# 03_GSM_GPRS_GPS.net
KiCad netlist of a schematic drawn in Altium Designer
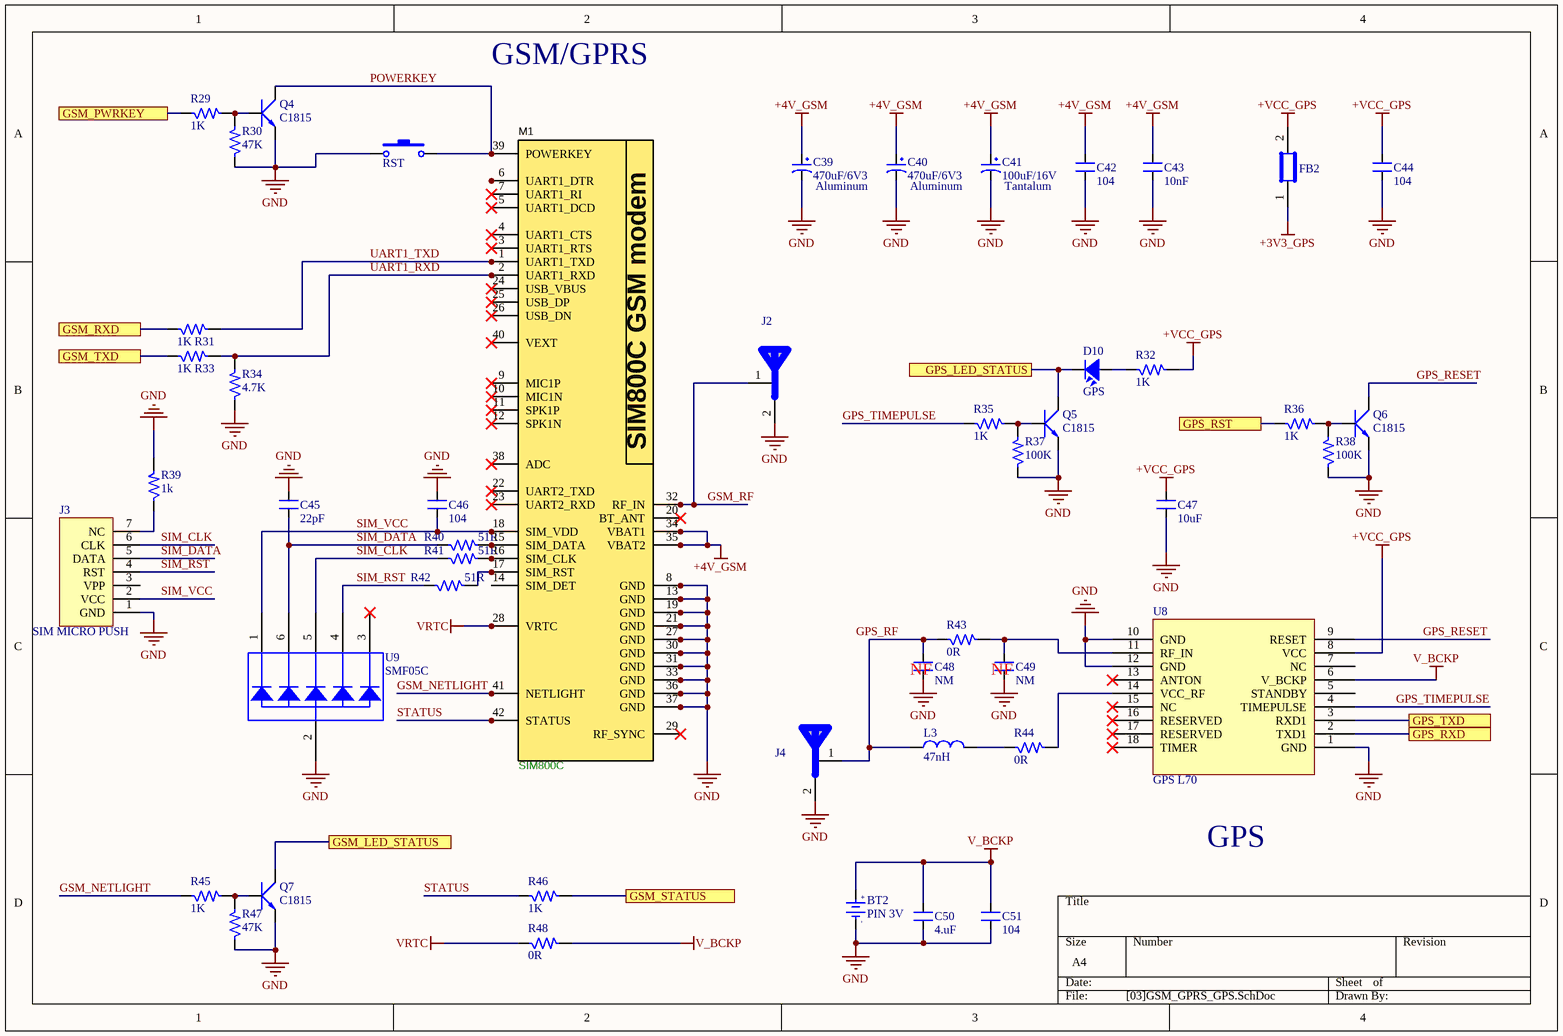
[diagram p0: [03]GSM_GPRS_GPS.SchDoc]

(export (version "E")
  (design (tool "Eeschema 10.0.6"))
  (components
    (comp (ref "BT2")
      (value "PIN 3V")
      (footprint "My Library:CR1220 SMD")
      (description "Battery 3VDC")
      (libsource (lib "GPS_Traking_V1_1") (part "PIN 3V"))
    )
    (comp (ref "C39")
      (value "470uF/6V3")
      (footprint "C_Alu_6.3x7.7")
      (description "Cap Aluminum")
      (libsource (lib "GPS_Traking_V1_1") (part "C-Alu-Tantalum"))
    )
    (comp (ref "C40")
      (value "470uF/6V3")
      (footprint "C_Alu_6.3x7.7")
      (description "Cap Aluminum")
      (libsource (lib "GPS_Traking_V1_1") (part "C-Alu-Tantalum"))
    )
    (comp (ref "C41")
      (value "100uF/16V")
      (footprint "C_7343_40")
      (description "Cap Tantalum 7343")
      (libsource (lib "GPS_Traking_V1_1") (part "C-Alu-Tantalum"))
    )
    (comp (ref "C42")
      (value "104")
      (footprint "CAP_0805")
      (description "Cap SMD")
      (libsource (lib "GPS_Traking_V1_1") (part "CM"))
    )
    (comp (ref "C43")
      (value "10nF")
      (footprint "CAP_0805")
      (description "Cap SMD")
      (libsource (lib "GPS_Traking_V1_1") (part "CM"))
    )
    (comp (ref "C44")
      (value "104")
      (footprint "CAP_0805")
      (description "Cap SMD")
      (libsource (lib "GPS_Traking_V1_1") (part "CM"))
    )
    (comp (ref "C45")
      (value "22pF")
      (footprint "C0603 SMT")
      (description "Cap SMD")
      (libsource (lib "GPS_Traking_V1_1") (part "CM"))
    )
    (comp (ref "C46")
      (value "104")
      (footprint "C0603 SMT")
      (description "Cap SMD")
      (libsource (lib "GPS_Traking_V1_1") (part "CM"))
    )
    (comp (ref "C47")
      (value "10uF")
      (footprint "CAP_0805")
      (description "Cap SMD")
      (libsource (lib "GPS_Traking_V1_1") (part "CM"))
    )
    (comp (ref "C48")
      (value "NM")
      (footprint "C0603 SMT")
      (description "Cap SMD")
      (libsource (lib "GPS_Traking_V1_1") (part "CM"))
    )
    (comp (ref "C49")
      (value "NM")
      (footprint "C0603 SMT")
      (description "Cap SMD")
      (libsource (lib "GPS_Traking_V1_1") (part "CM"))
    )
    (comp (ref "C50")
      (value "4.uF")
      (footprint "SM-1210")
      (description "Cap SMD")
      (libsource (lib "GPS_Traking_V1_1") (part "CM"))
    )
    (comp (ref "C51")
      (value "104")
      (footprint "CAP_0805")
      (description "Cap SMD")
      (libsource (lib "GPS_Traking_V1_1") (part "CM"))
    )
    (comp (ref "D10")
      (value "GPS")
      (footprint "LED-0805-Red")
      (description "LED Single colour Green and Red")
      (libsource (lib "GPS_Traking_V1_1") (part "LED"))
    )
    (comp (ref "FB2")
      (value "BLM21PG600SN1D")
      (footprint "R0805")
      (description "Ferrite Bead")
      (libsource (lib "GPS_Traking_V1_1") (part "Ferrite Bead"))
    )
    (comp (ref "J2")
      (value "GPS_ANTENNA")
      (footprint "Antenna-MCX5.08-H5")
      (libsource (lib "GPS_Traking_V1_1") (part "ANTEN"))
    )
    (comp (ref "J3")
      (value "SIM MICRO PUSH")
      (footprint "My Library:MICROSIM_PUSH")
      (libsource (lib "My Library") (part "SIM MICRO PUSH"))
    )
    (comp (ref "J4")
      (value "GPS_ANTENNA")
      (footprint "Antenna-MCX5.08-H5")
      (libsource (lib "GPS_Traking_V1_1") (part "ANTEN"))
    )
    (comp (ref "L3")
      (value "47nH")
      (footprint "RES-SMD-0805")
      (description "Inductor")
      (libsource (lib "GPS_Traking_V1_1") (part "L1"))
    )
    (comp (ref "M1")
      (value "SIM800C")
      (footprint "SIM800C")
      (libsource (lib "GPS_Traking_V1_1") (part "SIM800C"))
    )
    (comp (ref "Q4")
      (value "C1815")
      (footprint "SOT23B")
      (description "NPN 600mW, ECB")
      (libsource (lib "GPS_Traking_V1_1") (part "C1815"))
    )
    (comp (ref "Q5")
      (value "C1815")
      (footprint "SOT23B")
      (description "NPN 600mW, ECB")
      (libsource (lib "GPS_Traking_V1_1") (part "C1815"))
    )
    (comp (ref "Q6")
      (value "C1815")
      (footprint "SOT23B")
      (description "NPN 600mW, ECB")
      (libsource (lib "GPS_Traking_V1_1") (part "C1815"))
    )
    (comp (ref "Q7")
      (value "C1815")
      (footprint "SOT23B")
      (description "NPN 600mW, ECB")
      (libsource (lib "GPS_Traking_V1_1") (part "C1815"))
    )
    (comp (ref "R29")
      (value "1K")
      (footprint "R0603 -SMT")
      (description "Resistor SMD")
      (libsource (lib "GPS_Traking_V1_1") (part "RM"))
    )
    (comp (ref "R30")
      (value "47K")
      (footprint "R0603 -SMT")
      (description "Resistor SMD")
      (libsource (lib "GPS_Traking_V1_1") (part "RM"))
    )
    (comp (ref "R31")
      (value "1K")
      (footprint "R0603 -SMT")
      (description "Resistor SMD")
      (libsource (lib "GPS_Traking_V1_1") (part "RM"))
    )
    (comp (ref "R32")
      (value "1K")
      (footprint "RES-SMD-0805")
      (description "Resistor SMD")
      (libsource (lib "GPS_Traking_V1_1") (part "RM"))
    )
    (comp (ref "R33")
      (value "1K")
      (footprint "R0603 -SMT")
      (description "Resistor SMD")
      (libsource (lib "GPS_Traking_V1_1") (part "RM"))
    )
    (comp (ref "R34")
      (value "4.7K")
      (footprint "R0603 -SMT")
      (description "Resistor SMD")
      (libsource (lib "GPS_Traking_V1_1") (part "RM"))
    )
    (comp (ref "R35")
      (value "1K")
      (footprint "RES-SMD-0805")
      (description "Resistor SMD")
      (libsource (lib "GPS_Traking_V1_1") (part "RM"))
    )
    (comp (ref "R36")
      (value "1K")
      (footprint "RES-SMD-0805")
      (description "Resistor SMD")
      (libsource (lib "GPS_Traking_V1_1") (part "RM"))
    )
    (comp (ref "R37")
      (value "100K")
      (footprint "RES-SMD-0805")
      (description "Resistor SMD")
      (libsource (lib "GPS_Traking_V1_1") (part "RM"))
    )
    (comp (ref "R38")
      (value "100K")
      (footprint "RES-SMD-0805")
      (description "Resistor SMD")
      (libsource (lib "GPS_Traking_V1_1") (part "RM"))
    )
    (comp (ref "R39")
      (value "1k")
      (footprint "RES-SMD-0805")
      (description "Resistor SMD")
      (libsource (lib "GPS_Traking_V1_1") (part "RM"))
    )
    (comp (ref "R40")
      (value "51R")
      (footprint "R0603 -SMT")
      (description "Resistor SMD")
      (libsource (lib "GPS_Traking_V1_1") (part "RM"))
    )
    (comp (ref "R41")
      (value "51R")
      (footprint "R0603 -SMT")
      (description "Resistor SMD")
      (libsource (lib "GPS_Traking_V1_1") (part "RM"))
    )
    (comp (ref "R42")
      (value "51R")
      (footprint "R0603 -SMT")
      (description "Resistor SMD")
      (libsource (lib "GPS_Traking_V1_1") (part "RM"))
    )
    (comp (ref "R43")
      (value "0R")
      (footprint "R0603 -SMT")
      (description "Resistor SMD")
      (libsource (lib "GPS_Traking_V1_1") (part "RM"))
    )
    (comp (ref "R44")
      (value "0R")
      (footprint "R0603 -SMT")
      (description "Resistor SMD")
      (libsource (lib "GPS_Traking_V1_1") (part "RM"))
    )
    (comp (ref "R45")
      (value "1K")
      (footprint "R0603 -SMT")
      (description "Resistor SMD")
      (libsource (lib "GPS_Traking_V1_1") (part "RM"))
    )
    (comp (ref "R46")
      (value "1K")
      (footprint "R0603 -SMT")
      (description "Resistor SMD")
      (libsource (lib "GPS_Traking_V1_1") (part "RM"))
    )
    (comp (ref "R47")
      (value "47K")
      (footprint "R0603 -SMT")
      (description "Resistor SMD")
      (libsource (lib "GPS_Traking_V1_1") (part "RM"))
    )
    (comp (ref "R48")
      (value "0R")
      (footprint "RES-SMD-0805")
      (description "Resistor SMD")
      (libsource (lib "GPS_Traking_V1_1") (part "RM"))
    )
    (comp (ref "RST")
      (value "SW-SMD")
      (footprint "SW-SMD")
      (description "Switch")
      (fields (field (name "PUBLISHER") "Altium Limited"))
      (libsource (lib "My Library") (part "SW-SMD"))
    )
    (comp (ref "U8")
      (value "GPS L70")
      (footprint "GPS L70")
      (libsource (lib "GPS_Traking_V1_1") (part "GPS L70"))
    )
    (comp (ref "U9")
      (value "SMF05C")
      (footprint "SOT_363_6")
      (description "ESD Protection")
      (libsource (lib "GPS_Traking_V1_1") (part "SMF05C"))
    )
  )
  (nets
    (net (code "1") (name "+3V3_GPS") (class "Default")
      (node (ref "FB2") (pin "1") (pinfunction "1_1") (pintype "passive"))
    )
    (net (code "2") (name "+4V_GSM") (class "Default")
      (node (ref "C39") (pin "1") (pinfunction "1_1") (pintype "passive"))
      (node (ref "C40") (pin "1") (pinfunction "1_1") (pintype "passive"))
      (node (ref "C41") (pin "1") (pinfunction "1_1") (pintype "passive"))
      (node (ref "C42") (pin "1") (pinfunction "1_1") (pintype "passive"))
      (node (ref "C43") (pin "1") (pinfunction "1_1") (pintype "passive"))
      (node (ref "M1") (pin "34") (pinfunction "VBAT1_34") (pintype "passive"))
      (node (ref "M1") (pin "35") (pinfunction "VBAT2_35") (pintype "passive"))
    )
    (net (code "3") (name "+VCC_GPS") (class "Default")
      (node (ref "C44") (pin "2") (pinfunction "2_2") (pintype "passive"))
      (node (ref "C47") (pin "2") (pinfunction "2_2") (pintype "passive"))
      (node (ref "FB2") (pin "2") (pinfunction "2_2") (pintype "passive"))
      (node (ref "R32") (pin "2") (pinfunction "2_2") (pintype "passive"))
      (node (ref "U8") (pin "8") (pinfunction "VCC_8") (pintype "passive"))
    )
    (net (code "4") (name "/GPS_LED_STATUS") (class "Default")
      (node (ref "D10") (pin "2") (pinfunction "2_2") (pintype "passive"))
      (node (ref "Q5") (pin "2") (pinfunction "C_2") (pintype "passive"))
    )
    (net (code "5") (name "/GPS_RESET") (class "Default")
      (node (ref "Q6") (pin "2") (pinfunction "C_2") (pintype "passive"))
      (node (ref "U8") (pin "9") (pinfunction "RESET_9") (pintype "passive"))
    )
    (net (code "7") (name "/GPS_RST") (class "Default")
      (node (ref "R36") (pin "1") (pinfunction "1_1") (pintype "passive"))
    )
    (net (code "8") (name "/GPS_RXD") (class "Default")
      (node (ref "U8") (pin "2") (pinfunction "TXD1_2") (pintype "passive"))
    )
    (net (code "9") (name "/GPS_TIMEPULSE") (class "Default")
      (node (ref "R35") (pin "1") (pinfunction "1_1") (pintype "passive"))
      (node (ref "U8") (pin "4") (pinfunction "TIMEPULSE_4") (pintype "passive"))
    )
    (net (code "10") (name "/GPS_TXD") (class "Default")
      (node (ref "U8") (pin "3") (pinfunction "RXD1_3") (pintype "passive"))
    )
    (net (code "11") (name "/GSM_LED_STATUS") (class "Default")
      (node (ref "Q7") (pin "2") (pinfunction "C_2") (pintype "passive"))
    )
    (net (code "12") (name "/GSM_NETLIGHT") (class "Default")
      (node (ref "M1") (pin "41") (pinfunction "NETLIGHT_41") (pintype "passive"))
      (node (ref "R45") (pin "1") (pinfunction "1_1") (pintype "passive"))
    )
    (net (code "13") (name "/GSM_PWRKEY") (class "Default")
      (node (ref "R29") (pin "1") (pinfunction "1_1") (pintype "passive"))
    )
    (net (code "14") (name "/GSM_RF") (class "Default")
      (node (ref "J2") (pin "1") (pinfunction "GND_1") (pintype "passive"))
      (node (ref "M1") (pin "32") (pinfunction "RF_IN_32") (pintype "passive"))
    )
    (net (code "15") (name "/GSM_RXD") (class "Default")
      (node (ref "R31") (pin "1") (pinfunction "1_1") (pintype "passive"))
    )
    (net (code "16") (name "/GSM_STATUS") (class "Default")
      (node (ref "R46") (pin "2") (pinfunction "2_2") (pintype "passive"))
    )
    (net (code "17") (name "/GSM_TXD") (class "Default")
      (node (ref "R33") (pin "1") (pinfunction "1_1") (pintype "passive"))
    )
    (net (code "18") (name "/POWERKEY") (class "Default")
      (node (ref "M1") (pin "39") (pinfunction "POWERKEY_39") (pintype "passive"))
      (node (ref "Q4") (pin "2") (pinfunction "C_2") (pintype "passive"))
      (node (ref "RST") (pin "2") (pinfunction "2_2") (pintype "passive"))
    )
    (net (code "19") (name "/SIM_CLK") (class "Default")
      (node (ref "J3") (pin "6") (pinfunction "CLK_6") (pintype "passive"))
      (node (ref "R41") (pin "1") (pinfunction "1_1") (pintype "passive"))
      (node (ref "U9") (pin "5") (pinfunction "K4_5") (pintype "power_in"))
    )
    (net (code "20") (name "/SIM_DATA") (class "Default")
      (node (ref "C45") (pin "1") (pinfunction "1_1") (pintype "passive"))
      (node (ref "J3") (pin "5") (pinfunction "DATA_5") (pintype "passive"))
      (node (ref "R40") (pin "1") (pinfunction "1_1") (pintype "passive"))
      (node (ref "U9") (pin "6") (pinfunction "K5_6") (pintype "passive"))
    )
    (net (code "21") (name "/SIM_RST") (class "Default")
      (node (ref "J3") (pin "4") (pinfunction "RST_4") (pintype "passive"))
      (node (ref "R42") (pin "1") (pinfunction "1_1") (pintype "passive"))
      (node (ref "U9") (pin "4") (pinfunction "K3_4") (pintype "passive"))
    )
    (net (code "22") (name "/SIM_VCC") (class "Default")
      (node (ref "C46") (pin "1") (pinfunction "1_1") (pintype "passive"))
      (node (ref "J3") (pin "2") (pinfunction "VCC_2") (pintype "passive"))
      (node (ref "M1") (pin "18") (pinfunction "SIM_VDD_18") (pintype "passive"))
      (node (ref "U9") (pin "1") (pinfunction "K1_1") (pintype "passive"))
    )
    (net (code "23") (name "/STATUS") (class "Default")
      (node (ref "M1") (pin "42") (pinfunction "STATUS_42") (pintype "passive"))
      (node (ref "R46") (pin "1") (pinfunction "1_1") (pintype "passive"))
    )
    (net (code "24") (name "/UART1_RXD") (class "Default")
      (node (ref "M1") (pin "2") (pinfunction "UART1_RXD_2") (pintype "passive"))
      (node (ref "R33") (pin "2") (pinfunction "2_2") (pintype "passive"))
      (node (ref "R34") (pin "2") (pinfunction "2_2") (pintype "passive"))
    )
    (net (code "25") (name "/UART1_TXD") (class "Default")
      (node (ref "M1") (pin "1") (pinfunction "UART1_TXD_1") (pintype "passive"))
      (node (ref "R31") (pin "2") (pinfunction "2_2") (pintype "passive"))
    )
    (net (code "26") (name "GND") (class "Default")
      (node (ref "BT2") (pin "2") (pinfunction "GND_2") (pintype "passive"))
      (node (ref "C39") (pin "2") (pinfunction "2_2") (pintype "passive"))
      (node (ref "C40") (pin "2") (pinfunction "2_2") (pintype "passive"))
      (node (ref "C41") (pin "2") (pinfunction "2_2") (pintype "passive"))
      (node (ref "C42") (pin "2") (pinfunction "2_2") (pintype "passive"))
      (node (ref "C43") (pin "2") (pinfunction "2_2") (pintype "passive"))
      (node (ref "C44") (pin "1") (pinfunction "1_1") (pintype "passive"))
      (node (ref "C45") (pin "2") (pinfunction "2_2") (pintype "passive"))
      (node (ref "C46") (pin "2") (pinfunction "2_2") (pintype "passive"))
      (node (ref "C47") (pin "1") (pinfunction "1_1") (pintype "passive"))
      (node (ref "C48") (pin "1") (pinfunction "1_1") (pintype "passive"))
      (node (ref "C49") (pin "1") (pinfunction "1_1") (pintype "passive"))
      (node (ref "C50") (pin "1") (pinfunction "1_1") (pintype "passive"))
      (node (ref "C51") (pin "1") (pinfunction "1_1") (pintype "passive"))
      (node (ref "J2") (pin "2") (pinfunction "GND_2") (pintype "passive"))
      (node (ref "J3") (pin "1") (pinfunction "GND_1") (pintype "passive"))
      (node (ref "J4") (pin "2") (pinfunction "GND_2") (pintype "passive"))
      (node (ref "M1") (pin "13") (pinfunction "GND_13") (pintype "passive"))
      (node (ref "M1") (pin "19") (pinfunction "GND_19") (pintype "passive"))
      (node (ref "M1") (pin "21") (pinfunction "GND_21") (pintype "passive"))
      (node (ref "M1") (pin "27") (pinfunction "GND_27") (pintype "passive"))
      (node (ref "M1") (pin "30") (pinfunction "GND_30") (pintype "passive"))
      (node (ref "M1") (pin "31") (pinfunction "GND_31") (pintype "passive"))
      (node (ref "M1") (pin "33") (pinfunction "GND_33") (pintype "passive"))
      (node (ref "M1") (pin "36") (pinfunction "GND_36") (pintype "passive"))
      (node (ref "M1") (pin "37") (pinfunction "GND_37") (pintype "passive"))
      (node (ref "M1") (pin "8") (pinfunction "GND_8") (pintype "passive"))
      (node (ref "Q4") (pin "1") (pinfunction "E_1") (pintype "passive"))
      (node (ref "Q5") (pin "1") (pinfunction "E_1") (pintype "passive"))
      (node (ref "Q6") (pin "1") (pinfunction "E_1") (pintype "passive"))
      (node (ref "Q7") (pin "1") (pinfunction "E_1") (pintype "passive"))
      (node (ref "R30") (pin "1") (pinfunction "1_1") (pintype "passive"))
      (node (ref "R34") (pin "1") (pinfunction "1_1") (pintype "passive"))
      (node (ref "R37") (pin "1") (pinfunction "1_1") (pintype "passive"))
      (node (ref "R38") (pin "1") (pinfunction "1_1") (pintype "passive"))
      (node (ref "R39") (pin "2") (pinfunction "2_2") (pintype "passive"))
      (node (ref "R47") (pin "1") (pinfunction "1_1") (pintype "passive"))
      (node (ref "RST") (pin "1") (pinfunction "1_1") (pintype "passive"))
      (node (ref "U8") (pin "1") (pinfunction "GND_1") (pintype "passive"))
      (node (ref "U8") (pin "10") (pinfunction "GND_10") (pintype "passive"))
      (node (ref "U8") (pin "12") (pinfunction "GND_12") (pintype "passive"))
      (node (ref "U9") (pin "2") (pinfunction "A_2") (pintype "power_in"))
    )
    (net (code "27") (name "Net-(C48-Pad2)") (class "Default")
      (node (ref "C48") (pin "2") (pinfunction "2_2") (pintype "passive"))
      (node (ref "J4") (pin "1") (pinfunction "GND_1") (pintype "passive"))
      (node (ref "L3") (pin "1") (pinfunction "1_1") (pintype "passive"))
      (node (ref "R43") (pin "1") (pinfunction "1_1") (pintype "passive"))
    )
    (net (code "28") (name "Net-(D10-Pad1)") (class "Default")
      (node (ref "D10") (pin "1") (pinfunction "1_1") (pintype "passive"))
      (node (ref "R32") (pin "1") (pinfunction "1_1") (pintype "passive"))
    )
    (net (code "29") (name "Net-(J3-NC)") (class "Default")
      (node (ref "J3") (pin "7") (pinfunction "NC_7") (pintype "passive"))
      (node (ref "R39") (pin "1") (pinfunction "1_1") (pintype "passive"))
    )
    (net (code "30") (name "Net-(L3-Pad2)") (class "Default")
      (node (ref "L3") (pin "2") (pinfunction "2_2") (pintype "passive"))
      (node (ref "R44") (pin "1") (pinfunction "1_1") (pintype "passive"))
    )
    (net (code "31") (name "Net-(M1-SIM_CLK)") (class "Default")
      (node (ref "M1") (pin "16") (pinfunction "SIM_CLK_16") (pintype "passive"))
      (node (ref "R41") (pin "2") (pinfunction "2_2") (pintype "passive"))
    )
    (net (code "32") (name "Net-(M1-SIM_DATA)") (class "Default")
      (node (ref "M1") (pin "15") (pinfunction "SIM_DATA_15") (pintype "passive"))
      (node (ref "R40") (pin "2") (pinfunction "2_2") (pintype "passive"))
    )
    (net (code "33") (name "Net-(M1-SIM_RST)") (class "Default")
      (node (ref "M1") (pin "17") (pinfunction "SIM_RST_17") (pintype "passive"))
      (node (ref "R42") (pin "2") (pinfunction "2_2") (pintype "passive"))
    )
    (net (code "34") (name "Net-(Q4-B)") (class "Default")
      (node (ref "Q4") (pin "3") (pinfunction "B_3") (pintype "passive"))
      (node (ref "R29") (pin "2") (pinfunction "2_2") (pintype "passive"))
      (node (ref "R30") (pin "2") (pinfunction "2_2") (pintype "passive"))
    )
    (net (code "35") (name "Net-(Q5-B)") (class "Default")
      (node (ref "Q5") (pin "3") (pinfunction "B_3") (pintype "passive"))
      (node (ref "R35") (pin "2") (pinfunction "2_2") (pintype "passive"))
      (node (ref "R37") (pin "2") (pinfunction "2_2") (pintype "passive"))
    )
    (net (code "36") (name "Net-(Q6-B)") (class "Default")
      (node (ref "Q6") (pin "3") (pinfunction "B_3") (pintype "passive"))
      (node (ref "R36") (pin "2") (pinfunction "2_2") (pintype "passive"))
      (node (ref "R38") (pin "2") (pinfunction "2_2") (pintype "passive"))
    )
    (net (code "37") (name "Net-(Q7-B)") (class "Default")
      (node (ref "Q7") (pin "3") (pinfunction "B_3") (pintype "passive"))
      (node (ref "R45") (pin "2") (pinfunction "2_2") (pintype "passive"))
      (node (ref "R47") (pin "2") (pinfunction "2_2") (pintype "passive"))
    )
    (net (code "38") (name "Net-(U8-RF_IN)") (class "Default")
      (node (ref "C49") (pin "2") (pinfunction "2_2") (pintype "passive"))
      (node (ref "R43") (pin "2") (pinfunction "2_2") (pintype "passive"))
      (node (ref "U8") (pin "11") (pinfunction "RF_IN_11") (pintype "passive"))
    )
    (net (code "39") (name "Net-(U8-VCC_RF)") (class "Default")
      (node (ref "R44") (pin "2") (pinfunction "2_2") (pintype "passive"))
      (node (ref "U8") (pin "14") (pinfunction "VCC_RF_14") (pintype "passive"))
    )
    (net (code "40") (name "VRTC") (class "Default")
      (node (ref "M1") (pin "28") (pinfunction "VRTC_28") (pintype "passive"))
      (node (ref "R48") (pin "1") (pinfunction "1_1") (pintype "passive"))
    )
    (net (code "41") (name "V_BCKP") (class "Default")
      (node (ref "BT2") (pin "1") (pinfunction "+3V_1") (pintype "passive"))
      (node (ref "C50") (pin "2") (pinfunction "2_2") (pintype "passive"))
      (node (ref "C51") (pin "2") (pinfunction "2_2") (pintype "passive"))
      (node (ref "R48") (pin "2") (pinfunction "2_2") (pintype "passive"))
      (node (ref "U8") (pin "6") (pinfunction "V_BCKP_6") (pintype "passive"))
    )
    (net (code "42") (name "unconnected-(J3-VPP-Pad3)") (class "Default")
      (node (ref "J3") (pin "3") (pinfunction "VPP_3") (pintype "passive"))
    )
    (net (code "43") (name "unconnected-(M1-ADC-Pad38)") (class "Default")
      (node (ref "M1") (pin "38") (pinfunction "ADC_38") (pintype "passive+no_connect"))
    )
    (net (code "44") (name "unconnected-(M1-BT_ANT-Pad20)") (class "Default")
      (node (ref "M1") (pin "20") (pinfunction "BT_ANT_20") (pintype "passive+no_connect"))
    )
    (net (code "45") (name "unconnected-(M1-MIC1N-Pad10)") (class "Default")
      (node (ref "M1") (pin "10") (pinfunction "MIC1N_10") (pintype "passive+no_connect"))
    )
    (net (code "46") (name "unconnected-(M1-MIC1P-Pad9)") (class "Default")
      (node (ref "M1") (pin "9") (pinfunction "MIC1P_9") (pintype "passive+no_connect"))
    )
    (net (code "47") (name "unconnected-(M1-RF_SYNC-Pad29)") (class "Default")
      (node (ref "M1") (pin "29") (pinfunction "RF_SYNC_29") (pintype "passive+no_connect"))
    )
    (net (code "48") (name "unconnected-(M1-SIM_DET-Pad14)") (class "Default")
      (node (ref "M1") (pin "14") (pinfunction "SIM_DET_14") (pintype "passive"))
    )
    (net (code "49") (name "unconnected-(M1-SPK1N-Pad12)") (class "Default")
      (node (ref "M1") (pin "12") (pinfunction "SPK1N_12") (pintype "passive+no_connect"))
    )
    (net (code "50") (name "unconnected-(M1-SPK1P-Pad11)") (class "Default")
      (node (ref "M1") (pin "11") (pinfunction "SPK1P_11") (pintype "passive+no_connect"))
    )
    (net (code "51") (name "unconnected-(M1-UART1_CTS-Pad4)") (class "Default")
      (node (ref "M1") (pin "4") (pinfunction "UART1_CTS_4") (pintype "passive+no_connect"))
    )
    (net (code "52") (name "unconnected-(M1-UART1_DCD-Pad5)") (class "Default")
      (node (ref "M1") (pin "5") (pinfunction "UART1_DCD_5") (pintype "passive+no_connect"))
    )
    (net (code "53") (name "unconnected-(M1-UART1_DTR-Pad6)") (class "Default")
      (node (ref "M1") (pin "6") (pinfunction "UART1_DTR_6") (pintype "passive"))
    )
    (net (code "54") (name "unconnected-(M1-UART1_RI-Pad7)") (class "Default")
      (node (ref "M1") (pin "7") (pinfunction "UART1_RI_7") (pintype "passive+no_connect"))
    )
    (net (code "55") (name "unconnected-(M1-UART1_RTS-Pad3)") (class "Default")
      (node (ref "M1") (pin "3") (pinfunction "UART1_RTS_3") (pintype "passive+no_connect"))
    )
    (net (code "56") (name "unconnected-(M1-UART2_RXD-Pad23)") (class "Default")
      (node (ref "M1") (pin "23") (pinfunction "UART2_RXD_23") (pintype "passive+no_connect"))
    )
    (net (code "57") (name "unconnected-(M1-UART2_TXD-Pad22)") (class "Default")
      (node (ref "M1") (pin "22") (pinfunction "UART2_TXD_22") (pintype "passive+no_connect"))
    )
    (net (code "58") (name "unconnected-(M1-USB_DN-Pad26)") (class "Default")
      (node (ref "M1") (pin "26") (pinfunction "USB_DN_26") (pintype "passive+no_connect"))
    )
    (net (code "59") (name "unconnected-(M1-USB_DP-Pad25)") (class "Default")
      (node (ref "M1") (pin "25") (pinfunction "USB_DP_25") (pintype "passive+no_connect"))
    )
    (net (code "60") (name "unconnected-(M1-USB_VBUS-Pad24)") (class "Default")
      (node (ref "M1") (pin "24") (pinfunction "USB_VBUS_24") (pintype "passive+no_connect"))
    )
    (net (code "61") (name "unconnected-(M1-VEXT-Pad40)") (class "Default")
      (node (ref "M1") (pin "40") (pinfunction "VEXT_40") (pintype "passive+no_connect"))
    )
    (net (code "62") (name "unconnected-(U8-ANTON-Pad13)") (class "Default")
      (node (ref "U8") (pin "13") (pinfunction "ANTON_13") (pintype "passive+no_connect"))
    )
    (net (code "63") (name "unconnected-(U8-NC-Pad7)") (class "Default")
      (node (ref "U8") (pin "7") (pinfunction "NC_7") (pintype "passive"))
    )
    (net (code "64") (name "unconnected-(U8-NC-Pad15)") (class "Default")
      (node (ref "U8") (pin "15") (pinfunction "NC_15") (pintype "passive+no_connect"))
    )
    (net (code "65") (name "unconnected-(U8-RESERVED-Pad16)") (class "Default")
      (node (ref "U8") (pin "16") (pinfunction "RESERVED_16") (pintype "passive+no_connect"))
    )
    (net (code "66") (name "unconnected-(U8-RESERVED-Pad17)") (class "Default")
      (node (ref "U8") (pin "17") (pinfunction "RESERVED_17") (pintype "passive+no_connect"))
    )
    (net (code "67") (name "unconnected-(U8-STANDBY-Pad5)") (class "Default")
      (node (ref "U8") (pin "5") (pinfunction "STANDBY_5") (pintype "passive"))
    )
    (net (code "68") (name "unconnected-(U8-TIMER-Pad18)") (class "Default")
      (node (ref "U8") (pin "18") (pinfunction "TIMER_18") (pintype "passive+no_connect"))
    )
    (net (code "69") (name "unconnected-(U9-K2-Pad3)") (class "Default")
      (node (ref "U9") (pin "3") (pinfunction "K2_3") (pintype "passive+no_connect"))
    )
  )
)
